# Esquema.net
KiCad netlist of a schematic drawn in EAGLE
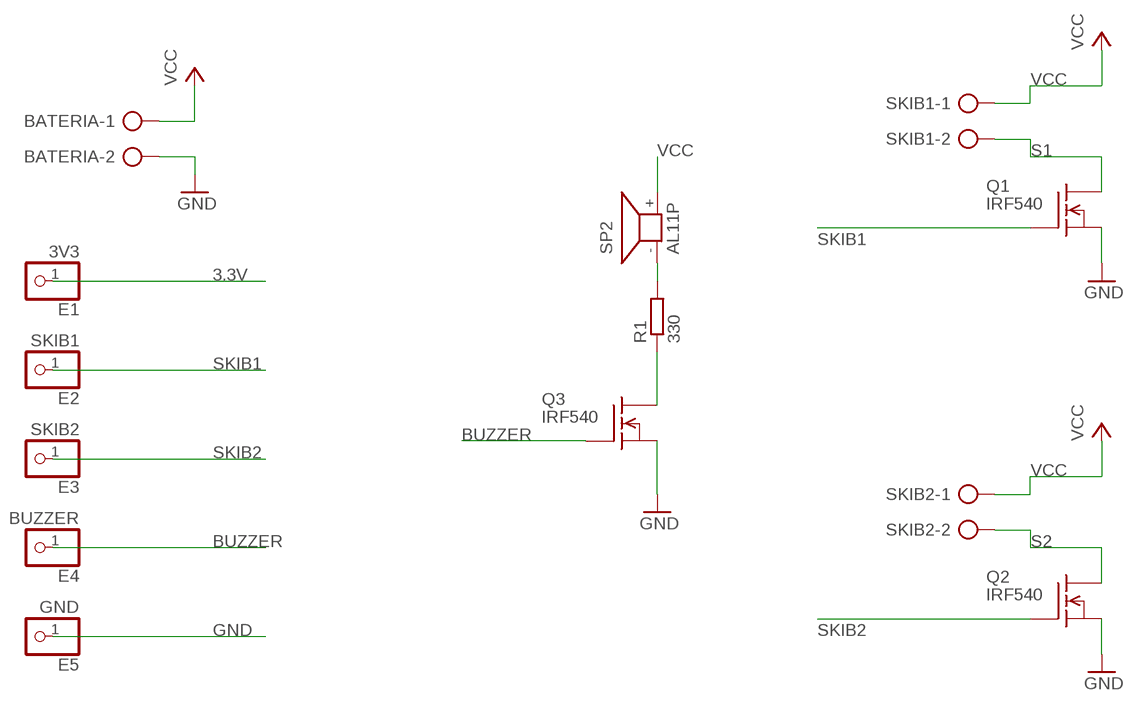
[diagram p0: schematic, sheet 1]

(export (version "E")
  (design (tool "Eeschema 10.0.6"))
  (components
    (comp (ref "BATERIA")
      (value "AK500/2-H")
      (footprint "eagle-import:AK500_2-H")
      (libsource (lib "eagle-import") (part "AK500/2-H"))
    )
    (comp (ref "E1")
      (value "3V3")
      (footprint "eagle-import:1X01")
      (libsource (lib "eagle-import") (part "PINHD-1X1"))
    )
    (comp (ref "E2")
      (value "SKIB1")
      (footprint "eagle-import:1X01")
      (libsource (lib "eagle-import") (part "PINHD-1X1"))
    )
    (comp (ref "E3")
      (value "SKIB2")
      (footprint "eagle-import:1X01")
      (libsource (lib "eagle-import") (part "PINHD-1X1"))
    )
    (comp (ref "E4")
      (value "BUZZER")
      (footprint "eagle-import:1X01")
      (libsource (lib "eagle-import") (part "PINHD-1X1"))
    )
    (comp (ref "E5")
      (value "GND")
      (footprint "eagle-import:1X01")
      (libsource (lib "eagle-import") (part "PINHD-1X1"))
    )
    (comp (ref "Q1")
      (value "IRF540")
      (footprint "eagle-import:TO220")
      (libsource (lib "eagle-import") (part "IRF540"))
    )
    (comp (ref "Q2")
      (value "IRF540")
      (footprint "eagle-import:TO220")
      (libsource (lib "eagle-import") (part "IRF540"))
    )
    (comp (ref "Q3")
      (value "IRF540")
      (footprint "eagle-import:TO220")
      (libsource (lib "eagle-import") (part "IRF540"))
    )
    (comp (ref "R1")
      (value "330")
      (footprint "eagle-import:0207_10")
      (libsource (lib "eagle-import") (part "R-EU_0207/10"))
    )
    (comp (ref "SKIB1")
      (value "AK500/2-H")
      (footprint "eagle-import:AK500_2-H")
      (libsource (lib "eagle-import") (part "AK500/2-H"))
    )
    (comp (ref "SKIB2")
      (value "AK500/2-H")
      (footprint "eagle-import:AK500_2-H")
      (libsource (lib "eagle-import") (part "AK500/2-H"))
    )
    (comp (ref "SP2")
      (value "AL11P")
      (footprint "eagle-import:AL11P")
      (libsource (lib "eagle-import") (part "AL11P"))
    )
  )
  (nets
    (net (code "1") (name "/3.3V") (class "Default")
      (node (ref "E1") (pin "1") (pinfunction "1_1") (pintype "passive"))
    )
    (net (code "2") (name "/BUZZER") (class "Default")
      (node (ref "E4") (pin "1") (pinfunction "1_1") (pintype "passive"))
      (node (ref "Q3") (pin "1") (pinfunction "G_1") (pintype "passive"))
    )
    (net (code "3") (name "/S1") (class "Default")
      (node (ref "Q1") (pin "2") (pinfunction "D_2") (pintype "passive"))
      (node (ref "SKIB1") (pin "2") (pinfunction "KL_2") (pintype "passive"))
    )
    (net (code "4") (name "/S2") (class "Default")
      (node (ref "Q2") (pin "2") (pinfunction "D_2") (pintype "passive"))
      (node (ref "SKIB2") (pin "2") (pinfunction "KL_2") (pintype "passive"))
    )
    (net (code "5") (name "/SKIB1") (class "Default")
      (node (ref "E2") (pin "1") (pinfunction "1_1") (pintype "passive"))
      (node (ref "Q1") (pin "1") (pinfunction "G_1") (pintype "passive"))
    )
    (net (code "6") (name "/SKIB2") (class "Default")
      (node (ref "E3") (pin "1") (pinfunction "1_1") (pintype "passive"))
      (node (ref "Q2") (pin "1") (pinfunction "G_1") (pintype "passive"))
    )
    (net (code "7") (name "GND") (class "Default")
      (node (ref "BATERIA") (pin "2") (pinfunction "KL_2") (pintype "passive"))
      (node (ref "E5") (pin "1") (pinfunction "1_1") (pintype "passive"))
      (node (ref "Q1") (pin "3") (pinfunction "S_3") (pintype "passive"))
      (node (ref "Q2") (pin "3") (pinfunction "S_3") (pintype "passive"))
      (node (ref "Q3") (pin "3") (pinfunction "S_3") (pintype "passive"))
    )
    (net (code "8") (name "Net-(Q3-D)") (class "Default")
      (node (ref "Q3") (pin "2") (pinfunction "D_2") (pintype "passive"))
      (node (ref "R1") (pin "1") (pinfunction "1_1") (pintype "passive"))
    )
    (net (code "9") (name "Net-(SP2-1)") (class "Default")
      (node (ref "R1") (pin "2") (pinfunction "2_2") (pintype "passive"))
      (node (ref "SP2") (pin "-") (pinfunction "1_-") (pintype "passive"))
    )
    (net (code "10") (name "VCC") (class "Default")
      (node (ref "BATERIA") (pin "1") (pinfunction "KL_1") (pintype "passive"))
      (node (ref "SKIB1") (pin "1") (pinfunction "KL_1") (pintype "passive"))
      (node (ref "SKIB2") (pin "1") (pinfunction "KL_1") (pintype "passive"))
      (node (ref "SP2") (pin "+") (pinfunction "2_+") (pintype "passive"))
    )
  )
)
